# IDE_CF.net
KiCad netlist of a schematic drawn in Altium Designer
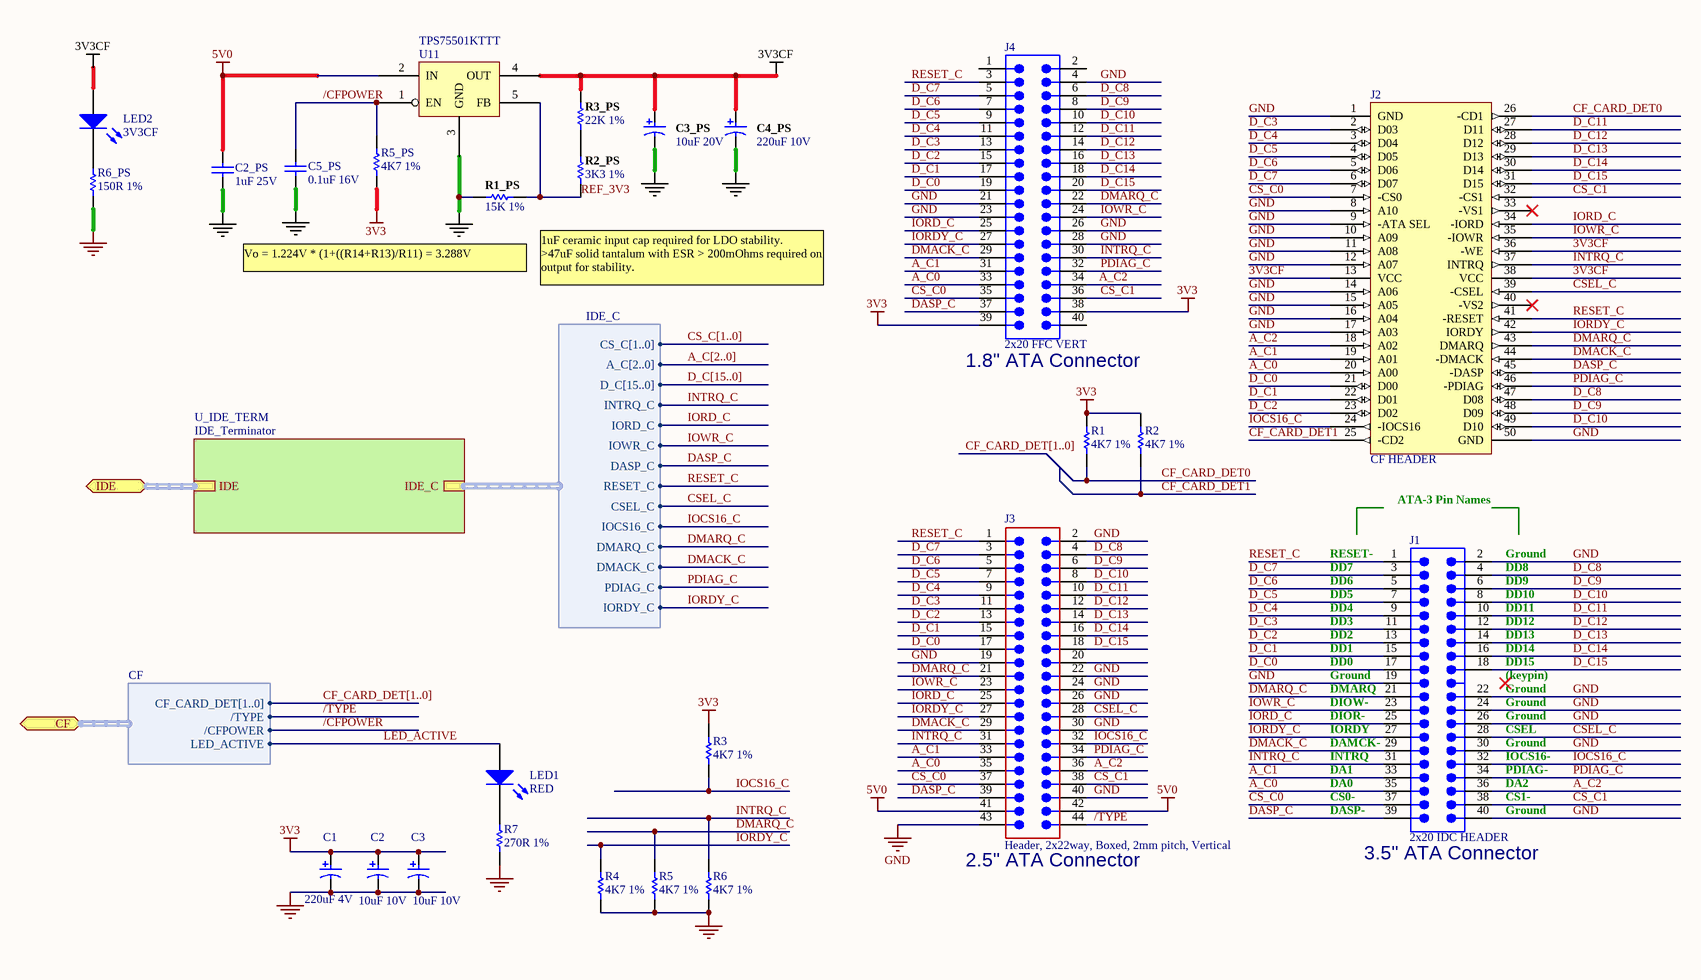
[diagram p0: IDE_CF.SchDoc]

(export (version "E")
  (design (tool "Eeschema 10.0.6"))
  (components
    (comp (ref "C1")
      (value "220uF 4V")
      (footprint "CAPC7343-STAR")
      (description "Capacitor, Tantalum, 220uF-4V-MCCT-D (7343)")
      (fields (field (name "TOLERANCE") "%"))
      (libsource (lib "AltiumDesignLibrary") (part "CAP-P"))
    )
    (comp (ref "C2")
      (value "10uF 10V")
      (footprint "CAPC3528-STAR")
      (description "Capacitor, Tantalum, 10uF 10V MCCT-B (3528)")
      (fields (field (name "TOLERANCE") "%"))
      (libsource (lib "AltiumDesignLibrary") (part "CAP-P"))
    )
    (comp (ref "C2_PS")
      (value "1uF 25V")
      (footprint "CAPC3216-STAR")
      (description "Capacitor, Ceramic, 1uF 10% 25V 1206 (3216) X7R")
      (fields (field (name "TOLERANCE") "10 %"))
      (libsource (lib "AltiumDesignLibrary") (part "CAP-NP"))
    )
    (comp (ref "C3")
      (value "10uF 10V")
      (footprint "CAPC3528-STAR")
      (description "Capacitor, Tantalum, 10uF 10V MCCT-B (3528)")
      (fields (field (name "TOLERANCE") "%"))
      (libsource (lib "AltiumDesignLibrary") (part "CAP-P"))
    )
    (comp (ref "C3_PS")
      (value "10uF 20V")
      (footprint "CAPC3528-STAR")
      (description "Capacitor, Tantalum, 10uF 10% 20V MCCT-B (3528)")
      (fields (field (name "TOLERANCE") "10 %"))
      (libsource (lib "AltiumDesignLibrary") (part "CAP-P"))
    )
    (comp (ref "C4_PS")
      (value "220uF 10V")
      (footprint "CAPC7343-STAR")
      (description "Capacitor, Tantalum, 220uF 10% 10V MCCT-D (7343-31)")
      (fields (field (name "TOLERANCE") "10 %"))
      (libsource (lib "AltiumDesignLibrary") (part "CAP-P"))
    )
    (comp (ref "C5_PS")
      (value "0.1uF 16V")
      (footprint "CAPC1005-STAR")
      (description "Capacitor, Ceramic, 0.1uF 10% 16V 0402 (1005) X7R")
      (fields (field (name "TOLERANCE") "10 %"))
      (libsource (lib "AltiumDesignLibrary") (part "CAP-NP"))
    )
    (comp (ref "J1")
      (value "2x20 IDC HEADER")
      (footprint "918540x324")
      (description "Header, Box 2 x 20 Pin Vertical 2.54mm Pitch")
      (libsource (lib "AltiumDesignLibrary") (part "CON-IDC-2x20-M-STR"))
    )
    (comp (ref "J2")
      (value "CF HEADER")
      (footprint "CF_SM0_635-6H50B")
      (description "Connector, Compact Flash Card Adaptor Top-side")
      (libsource (lib "AltiumDesignLibrary") (part "CON-CF"))
    )
    (comp (ref "J3")
      (value "Header, 2x22way, Boxed, 2mm pitch, Vertical")
      (footprint "HDR2X22-2mm")
      (libsource (lib "AltiumDesignLibrary") (part "CON-IDC-2x22-M-STR-2mm"))
    )
    (comp (ref "J4")
      (value "2x20 FFC VERT")
      (footprint "FFC40-05-VERT")
      (description "Header FFC, 2x20 pin Vertical, 0.5mm")
      (libsource (lib "AltiumDesignLibrary") (part "CON-FFC-2x20-VERT"))
    )
    (comp (ref "LED1")
      (value "RED")
      (footprint "LED2012-STAR")
      (description "LED, Red 0805 (2013) HSMH-C170")
      (libsource (lib "AltiumDesignLibrary") (part "DIO-LED-1S"))
    )
    (comp (ref "LED2")
      (value "3V3CF")
      (footprint "LED2012-STAR")
      (description "LED, Green 0805 (2012) KP-2012SGD")
      (libsource (lib "AltiumDesignLibrary") (part "DIO-LED-1S"))
    )
    (comp (ref "R1")
      (value "4K7 1%")
      (footprint "RESC1005-STAR")
      (description "Resistor, 4K7 1% 0402 (1005)")
      (fields (field (name "TOLERANCE") "1 %"))
      (libsource (lib "AltiumDesignLibrary") (part "RES"))
    )
    (comp (ref "R1_PS")
      (value "15K 1%")
      (footprint "RESC1005-STAR")
      (description "Resistor, 15K 1% 0402 (1005)")
      (fields (field (name "TOLERANCE") "1 %"))
      (libsource (lib "AltiumDesignLibrary") (part "RES"))
    )
    (comp (ref "R2")
      (value "4K7 1%")
      (footprint "RESC1005-STAR")
      (description "Resistor, 4K7 1% 0402 (1005)")
      (fields (field (name "TOLERANCE") "1 %"))
      (libsource (lib "AltiumDesignLibrary") (part "RES"))
    )
    (comp (ref "R2_PS")
      (value "3K3 1%")
      (footprint "RESC1005-STAR")
      (description "Resistor, 3K3 1% 0402 (1005)")
      (fields (field (name "TOLERANCE") "1 %"))
      (libsource (lib "AltiumDesignLibrary") (part "RES"))
    )
    (comp (ref "R3")
      (value "4K7 1%")
      (footprint "RESC1005-STAR")
      (description "Resistor, 4K7 1% 0402 (1005)")
      (fields (field (name "TOLERANCE") "1 %"))
      (libsource (lib "AltiumDesignLibrary") (part "RES"))
    )
    (comp (ref "R3_PS")
      (value "22K 1%")
      (footprint "RESC1005-STAR")
      (description "Resistor, 22K 1% 0402 (1005)")
      (fields (field (name "TOLERANCE") "1 %"))
      (libsource (lib "AltiumDesignLibrary") (part "RES"))
    )
    (comp (ref "R4")
      (value "4K7 1%")
      (footprint "RESC1005-STAR")
      (description "Resistor, 4K7 1% 0402 (1005)")
      (fields (field (name "TOLERANCE") "1 %"))
      (libsource (lib "AltiumDesignLibrary") (part "RES"))
    )
    (comp (ref "R5")
      (value "4K7 1%")
      (footprint "RESC1005-STAR")
      (description "Resistor, 4K7 1% 0402 (1005)")
      (fields (field (name "TOLERANCE") "1 %"))
      (libsource (lib "AltiumDesignLibrary") (part "RES"))
    )
    (comp (ref "R5_PS")
      (value "4K7 1%")
      (footprint "RESC1005-STAR")
      (description "Resistor, 4K7 1% 0402 (1005)")
      (fields (field (name "TOLERANCE") "1 %"))
      (libsource (lib "AltiumDesignLibrary") (part "RES"))
    )
    (comp (ref "R6")
      (value "4K7 1%")
      (footprint "RESC1005-STAR")
      (description "Resistor, 4K7 1% 0402 (1005)")
      (fields (field (name "TOLERANCE") "1 %"))
      (libsource (lib "AltiumDesignLibrary") (part "RES"))
    )
    (comp (ref "R6_PS")
      (value "150R 1%")
      (footprint "RESC1005-STAR")
      (description "Resistor, 150R 1% 0402 (1005)")
      (fields (field (name "TOLERANCE") "1 %"))
      (libsource (lib "AltiumDesignLibrary") (part "RES"))
    )
    (comp (ref "R7")
      (value "270R 1%")
      (footprint "RESC1005-STAR")
      (description "Resistor, 270R 1% 0402 (1005)")
      (fields (field (name "TOLERANCE") "1 %"))
      (libsource (lib "AltiumDesignLibrary") (part "RES"))
    )
    (comp (ref "U11")
      (value "TPS75501KTTT")
      (footprint "TO-263")
      (description "TPS75501KTTT, 5A, Low Dropout, Adjustable, Linear Voltage Regulator, TO-263")
      (libsource (lib "AltiumDesignLibrary") (part "TPS75501"))
    )
  )
  (nets
    (net (code "4") (name "/A_C0") (class "Default")
      (node (ref "J1") (pin "35") (pinfunction "35_35") (pintype "passive"))
      (node (ref "J2") (pin "20") (pinfunction "A00_20") (pintype "input"))
      (node (ref "J3") (pin "35") (pinfunction "35_35") (pintype "passive"))
      (node (ref "J4") (pin "33") (pinfunction "33_33") (pintype "passive"))
    )
    (net (code "5") (name "/A_C1") (class "Default")
      (node (ref "J1") (pin "33") (pinfunction "33_33") (pintype "passive"))
      (node (ref "J2") (pin "19") (pinfunction "A01_19") (pintype "input"))
      (node (ref "J3") (pin "33") (pinfunction "33_33") (pintype "passive"))
      (node (ref "J4") (pin "31") (pinfunction "31_31") (pintype "passive"))
    )
    (net (code "6") (name "/A_C2") (class "Default")
      (node (ref "J1") (pin "36") (pinfunction "36_36") (pintype "passive"))
      (node (ref "J2") (pin "18") (pinfunction "A02_18") (pintype "input"))
      (node (ref "J3") (pin "36") (pinfunction "36_36") (pintype "passive"))
      (node (ref "J4") (pin "34") (pinfunction "34_34") (pintype "passive"))
    )
    (net (code "8") (name "/CF_CARD_DET0") (class "Default")
      (node (ref "J2") (pin "26") (pinfunction "-CD1_26") (pintype "output"))
      (node (ref "R1") (pin "2") (pinfunction "2_2") (pintype "passive"))
    )
    (net (code "9") (name "/CF_CARD_DET1") (class "Default")
      (node (ref "J2") (pin "25") (pinfunction "-CD2_25") (pintype "output"))
      (node (ref "R2") (pin "2") (pinfunction "2_2") (pintype "passive"))
    )
    (net (code "11") (name "/CSEL_C") (class "Default")
      (node (ref "J1") (pin "28") (pinfunction "28_28") (pintype "passive"))
      (node (ref "J2") (pin "39") (pinfunction "-CSEL_39") (pintype "input"))
      (node (ref "J3") (pin "28") (pinfunction "28_28") (pintype "passive"))
    )
    (net (code "12") (name "/CS_C0") (class "Default")
      (node (ref "J1") (pin "37") (pinfunction "37_37") (pintype "passive"))
      (node (ref "J2") (pin "7") (pinfunction "-CS0_7") (pintype "input"))
      (node (ref "J3") (pin "37") (pinfunction "37_37") (pintype "passive"))
      (node (ref "J4") (pin "35") (pinfunction "35_35") (pintype "passive"))
    )
    (net (code "13") (name "/CS_C1") (class "Default")
      (node (ref "J1") (pin "38") (pinfunction "38_38") (pintype "passive"))
      (node (ref "J2") (pin "32") (pinfunction "-CS1_32") (pintype "input"))
      (node (ref "J3") (pin "38") (pinfunction "38_38") (pintype "passive"))
      (node (ref "J4") (pin "36") (pinfunction "36_36") (pintype "passive"))
    )
    (net (code "15") (name "/DASP_C") (class "Default")
      (node (ref "J1") (pin "39") (pinfunction "39_39") (pintype "passive"))
      (node (ref "J2") (pin "45") (pinfunction "-DASP_45") (pintype "bidirectional"))
      (node (ref "J3") (pin "39") (pinfunction "39_39") (pintype "passive"))
      (node (ref "J4") (pin "37") (pinfunction "37_37") (pintype "passive"))
    )
    (net (code "16") (name "/DMACK_C") (class "Default")
      (node (ref "J1") (pin "29") (pinfunction "29_29") (pintype "passive"))
      (node (ref "J2") (pin "44") (pinfunction "-DMACK_44") (pintype "input"))
      (node (ref "J3") (pin "29") (pinfunction "29_29") (pintype "passive"))
      (node (ref "J4") (pin "29") (pinfunction "29_29") (pintype "passive"))
    )
    (net (code "17") (name "/DMARQ_C") (class "Default")
      (node (ref "J1") (pin "21") (pinfunction "21_21") (pintype "passive"))
      (node (ref "J2") (pin "43") (pinfunction "DMARQ_43") (pintype "output"))
      (node (ref "J3") (pin "21") (pinfunction "21_21") (pintype "passive"))
      (node (ref "J4") (pin "22") (pinfunction "22_22") (pintype "passive"))
      (node (ref "R5") (pin "1") (pinfunction "1_1") (pintype "passive"))
    )
    (net (code "18") (name "/D_C0") (class "Default")
      (node (ref "J1") (pin "17") (pinfunction "17_17") (pintype "passive"))
      (node (ref "J2") (pin "21") (pinfunction "D00_21") (pintype "bidirectional"))
      (node (ref "J3") (pin "17") (pinfunction "17_17") (pintype "passive"))
      (node (ref "J4") (pin "19") (pinfunction "19_19") (pintype "passive"))
    )
    (net (code "19") (name "/D_C1") (class "Default")
      (node (ref "J1") (pin "15") (pinfunction "15_15") (pintype "passive"))
      (node (ref "J2") (pin "22") (pinfunction "D01_22") (pintype "bidirectional"))
      (node (ref "J3") (pin "15") (pinfunction "15_15") (pintype "passive"))
      (node (ref "J4") (pin "17") (pinfunction "17_17") (pintype "passive"))
    )
    (net (code "20") (name "/D_C2") (class "Default")
      (node (ref "J1") (pin "13") (pinfunction "13_13") (pintype "passive"))
      (node (ref "J2") (pin "23") (pinfunction "D02_23") (pintype "bidirectional"))
      (node (ref "J3") (pin "13") (pinfunction "13_13") (pintype "passive"))
      (node (ref "J4") (pin "15") (pinfunction "15_15") (pintype "passive"))
    )
    (net (code "21") (name "/D_C3") (class "Default")
      (node (ref "J1") (pin "11") (pinfunction "11_11") (pintype "passive"))
      (node (ref "J2") (pin "2") (pinfunction "D03_2") (pintype "bidirectional"))
      (node (ref "J3") (pin "11") (pinfunction "11_11") (pintype "passive"))
      (node (ref "J4") (pin "13") (pinfunction "13_13") (pintype "passive"))
    )
    (net (code "22") (name "/D_C4") (class "Default")
      (node (ref "J1") (pin "9") (pinfunction "9_9") (pintype "passive"))
      (node (ref "J2") (pin "3") (pinfunction "D04_3") (pintype "bidirectional"))
      (node (ref "J3") (pin "9") (pinfunction "9_9") (pintype "passive"))
      (node (ref "J4") (pin "11") (pinfunction "11_11") (pintype "passive"))
    )
    (net (code "23") (name "/D_C5") (class "Default")
      (node (ref "J1") (pin "7") (pinfunction "7_7") (pintype "passive"))
      (node (ref "J2") (pin "4") (pinfunction "D05_4") (pintype "bidirectional"))
      (node (ref "J3") (pin "7") (pinfunction "7_7") (pintype "passive"))
      (node (ref "J4") (pin "9") (pinfunction "9_9") (pintype "passive"))
    )
    (net (code "24") (name "/D_C6") (class "Default")
      (node (ref "J1") (pin "5") (pinfunction "5_5") (pintype "passive"))
      (node (ref "J2") (pin "5") (pinfunction "D06_5") (pintype "bidirectional"))
      (node (ref "J3") (pin "5") (pinfunction "5_5") (pintype "passive"))
      (node (ref "J4") (pin "7") (pinfunction "7_7") (pintype "passive"))
    )
    (net (code "25") (name "/D_C7") (class "Default")
      (node (ref "J1") (pin "3") (pinfunction "3_3") (pintype "passive"))
      (node (ref "J2") (pin "6") (pinfunction "D07_6") (pintype "bidirectional"))
      (node (ref "J3") (pin "3") (pinfunction "3_3") (pintype "passive"))
      (node (ref "J4") (pin "5") (pinfunction "5_5") (pintype "passive"))
    )
    (net (code "26") (name "/D_C8") (class "Default")
      (node (ref "J1") (pin "4") (pinfunction "4_4") (pintype "passive"))
      (node (ref "J2") (pin "47") (pinfunction "D08_47") (pintype "bidirectional"))
      (node (ref "J3") (pin "4") (pinfunction "4_4") (pintype "passive"))
      (node (ref "J4") (pin "6") (pinfunction "6_6") (pintype "passive"))
    )
    (net (code "27") (name "/D_C9") (class "Default")
      (node (ref "J1") (pin "6") (pinfunction "6_6") (pintype "passive"))
      (node (ref "J2") (pin "48") (pinfunction "D09_48") (pintype "bidirectional"))
      (node (ref "J3") (pin "6") (pinfunction "6_6") (pintype "passive"))
      (node (ref "J4") (pin "8") (pinfunction "8_8") (pintype "passive"))
    )
    (net (code "28") (name "/D_C10") (class "Default")
      (node (ref "J1") (pin "8") (pinfunction "8_8") (pintype "passive"))
      (node (ref "J2") (pin "49") (pinfunction "D10_49") (pintype "bidirectional"))
      (node (ref "J3") (pin "8") (pinfunction "8_8") (pintype "passive"))
      (node (ref "J4") (pin "10") (pinfunction "10_10") (pintype "passive"))
    )
    (net (code "29") (name "/D_C11") (class "Default")
      (node (ref "J1") (pin "10") (pinfunction "10_10") (pintype "passive"))
      (node (ref "J2") (pin "27") (pinfunction "D11_27") (pintype "bidirectional"))
      (node (ref "J3") (pin "10") (pinfunction "10_10") (pintype "passive"))
      (node (ref "J4") (pin "12") (pinfunction "12_12") (pintype "passive"))
    )
    (net (code "30") (name "/D_C12") (class "Default")
      (node (ref "J1") (pin "12") (pinfunction "12_12") (pintype "passive"))
      (node (ref "J2") (pin "28") (pinfunction "D12_28") (pintype "bidirectional"))
      (node (ref "J3") (pin "12") (pinfunction "12_12") (pintype "passive"))
      (node (ref "J4") (pin "14") (pinfunction "14_14") (pintype "passive"))
    )
    (net (code "31") (name "/D_C13") (class "Default")
      (node (ref "J1") (pin "14") (pinfunction "14_14") (pintype "passive"))
      (node (ref "J2") (pin "29") (pinfunction "D13_29") (pintype "bidirectional"))
      (node (ref "J3") (pin "14") (pinfunction "14_14") (pintype "passive"))
      (node (ref "J4") (pin "16") (pinfunction "16_16") (pintype "passive"))
    )
    (net (code "32") (name "/D_C14") (class "Default")
      (node (ref "J1") (pin "16") (pinfunction "16_16") (pintype "passive"))
      (node (ref "J2") (pin "30") (pinfunction "D14_30") (pintype "bidirectional"))
      (node (ref "J3") (pin "16") (pinfunction "16_16") (pintype "passive"))
      (node (ref "J4") (pin "18") (pinfunction "18_18") (pintype "passive"))
    )
    (net (code "33") (name "/D_C15") (class "Default")
      (node (ref "J1") (pin "18") (pinfunction "18_18") (pintype "passive"))
      (node (ref "J2") (pin "31") (pinfunction "D15_31") (pintype "bidirectional"))
      (node (ref "J3") (pin "18") (pinfunction "18_18") (pintype "passive"))
      (node (ref "J4") (pin "20") (pinfunction "20_20") (pintype "passive"))
    )
    (net (code "36") (name "/INTRQ_C") (class "Default")
      (node (ref "J1") (pin "31") (pinfunction "31_31") (pintype "passive"))
      (node (ref "J2") (pin "37") (pinfunction "INTRQ_37") (pintype "output"))
      (node (ref "J3") (pin "31") (pinfunction "31_31") (pintype "passive"))
      (node (ref "J4") (pin "30") (pinfunction "30_30") (pintype "passive"))
      (node (ref "R6") (pin "1") (pinfunction "1_1") (pintype "passive"))
    )
    (net (code "37") (name "/IOCS16_C") (class "Default")
      (node (ref "J1") (pin "32") (pinfunction "32_32") (pintype "passive"))
      (node (ref "J2") (pin "24") (pinfunction "-IOCS16_24") (pintype "output"))
      (node (ref "J3") (pin "32") (pinfunction "32_32") (pintype "passive"))
      (node (ref "R3") (pin "2") (pinfunction "2_2") (pintype "passive"))
    )
    (net (code "38") (name "/IORDY_C") (class "Default")
      (node (ref "J1") (pin "27") (pinfunction "27_27") (pintype "passive"))
      (node (ref "J2") (pin "42") (pinfunction "IORDY_42") (pintype "output"))
      (node (ref "J3") (pin "27") (pinfunction "27_27") (pintype "passive"))
      (node (ref "J4") (pin "27") (pinfunction "27_27") (pintype "passive"))
      (node (ref "R4") (pin "1") (pinfunction "1_1") (pintype "passive"))
    )
    (net (code "39") (name "/IORD_C") (class "Default")
      (node (ref "J1") (pin "25") (pinfunction "25_25") (pintype "passive"))
      (node (ref "J2") (pin "34") (pinfunction "-IORD_34") (pintype "input"))
      (node (ref "J3") (pin "25") (pinfunction "25_25") (pintype "passive"))
      (node (ref "J4") (pin "25") (pinfunction "25_25") (pintype "passive"))
    )
    (net (code "40") (name "/IOWR_C") (class "Default")
      (node (ref "J1") (pin "23") (pinfunction "23_23") (pintype "passive"))
      (node (ref "J2") (pin "35") (pinfunction "-IOWR_35") (pintype "input"))
      (node (ref "J3") (pin "23") (pinfunction "23_23") (pintype "passive"))
      (node (ref "J4") (pin "24") (pinfunction "24_24") (pintype "passive"))
    )
    (net (code "41") (name "/LED_ACTIVE") (class "Default")
      (node (ref "LED1") (pin "1") (pinfunction "A_1") (pintype "passive"))
    )
    (net (code "42") (name "/PDIAG_C") (class "Default")
      (node (ref "J1") (pin "34") (pinfunction "34_34") (pintype "passive"))
      (node (ref "J2") (pin "46") (pinfunction "-PDIAG_46") (pintype "bidirectional"))
      (node (ref "J3") (pin "34") (pinfunction "34_34") (pintype "passive"))
      (node (ref "J4") (pin "32") (pinfunction "32_32") (pintype "passive"))
    )
    (net (code "43") (name "/REF_3V3") (class "Default")
      (node (ref "R1_PS") (pin "2") (pinfunction "2_2") (pintype "passive"))
      (node (ref "R2_PS") (pin "1") (pinfunction "1_1") (pintype "passive"))
      (node (ref "U11") (pin "5") (pinfunction "FB_5") (pintype "passive"))
    )
    (net (code "44") (name "/RESET_C") (class "Default")
      (node (ref "J1") (pin "1") (pinfunction "1_1") (pintype "passive"))
      (node (ref "J2") (pin "41") (pinfunction "-RESET_41") (pintype "input"))
      (node (ref "J3") (pin "1") (pinfunction "1_1") (pintype "passive"))
      (node (ref "J4") (pin "3") (pinfunction "3_3") (pintype "passive"))
    )
    (net (code "47") (name "/{slash}CFPOWER") (class "Default")
      (node (ref "C5_PS") (pin "1") (pinfunction "1_1") (pintype "passive"))
      (node (ref "R5_PS") (pin "1") (pinfunction "1_1") (pintype "passive"))
      (node (ref "U11") (pin "1") (pinfunction "EN_1") (pintype "passive"))
    )
    (net (code "48") (name "/{slash}TYPE") (class "Default")
      (node (ref "J3") (pin "44") (pinfunction "44_44") (pintype "passive"))
    )
    (net (code "49") (name "3V3") (class "Default")
      (node (ref "C1") (pin "1") (pinfunction "1_1") (pintype "passive"))
      (node (ref "C2") (pin "1") (pinfunction "1_1") (pintype "passive"))
      (node (ref "C3") (pin "1") (pinfunction "1_1") (pintype "passive"))
      (node (ref "J4") (pin "38") (pinfunction "38_38") (pintype "passive"))
      (node (ref "J4") (pin "39") (pinfunction "39_39") (pintype "passive"))
      (node (ref "R1") (pin "1") (pinfunction "1_1") (pintype "passive"))
      (node (ref "R2") (pin "1") (pinfunction "1_1") (pintype "passive"))
      (node (ref "R3") (pin "1") (pinfunction "1_1") (pintype "passive"))
      (node (ref "R5_PS") (pin "2") (pinfunction "2_2") (pintype "passive"))
    )
    (net (code "50") (name "3V3CF") (class "Default")
      (node (ref "C3_PS") (pin "1") (pinfunction "1_1") (pintype "passive"))
      (node (ref "C4_PS") (pin "1") (pinfunction "1_1") (pintype "passive"))
      (node (ref "J2") (pin "13") (pinfunction "VCC_13") (pintype "power_in"))
      (node (ref "J2") (pin "36") (pinfunction "-WE_36") (pintype "input"))
      (node (ref "J2") (pin "38") (pinfunction "VCC_38") (pintype "power_in"))
      (node (ref "LED2") (pin "1") (pinfunction "A_1") (pintype "passive"))
      (node (ref "R3_PS") (pin "2") (pinfunction "2_2") (pintype "passive"))
      (node (ref "U11") (pin "4") (pinfunction "OUT_4") (pintype "passive"))
    )
    (net (code "51") (name "5V0") (class "Default")
      (node (ref "C2_PS") (pin "1") (pinfunction "1_1") (pintype "passive"))
      (node (ref "J3") (pin "41") (pinfunction "41_41") (pintype "passive"))
      (node (ref "J3") (pin "42") (pinfunction "42_42") (pintype "passive"))
      (node (ref "U11") (pin "2") (pinfunction "IN_2") (pintype "passive"))
    )
    (net (code "52") (name "GND") (class "Default")
      (node (ref "C1") (pin "2") (pinfunction "2_2") (pintype "passive"))
      (node (ref "C2") (pin "2") (pinfunction "2_2") (pintype "passive"))
      (node (ref "C2_PS") (pin "2") (pinfunction "2_2") (pintype "passive"))
      (node (ref "C3") (pin "2") (pinfunction "2_2") (pintype "passive"))
      (node (ref "C3_PS") (pin "2") (pinfunction "2_2") (pintype "passive"))
      (node (ref "C4_PS") (pin "2") (pinfunction "2_2") (pintype "passive"))
      (node (ref "C5_PS") (pin "2") (pinfunction "2_2") (pintype "passive"))
      (node (ref "J1") (pin "19") (pinfunction "19_19") (pintype "passive"))
      (node (ref "J1") (pin "2") (pinfunction "2_2") (pintype "passive"))
      (node (ref "J1") (pin "22") (pinfunction "22_22") (pintype "passive"))
      (node (ref "J1") (pin "24") (pinfunction "24_24") (pintype "passive"))
      (node (ref "J1") (pin "26") (pinfunction "26_26") (pintype "passive"))
      (node (ref "J1") (pin "30") (pinfunction "30_30") (pintype "passive"))
      (node (ref "J1") (pin "40") (pinfunction "40_40") (pintype "passive"))
      (node (ref "J2") (pin "1") (pinfunction "GND_1") (pintype "power_in"))
      (node (ref "J2") (pin "10") (pinfunction "A09_10") (pintype "input"))
      (node (ref "J2") (pin "11") (pinfunction "A08_11") (pintype "input"))
      (node (ref "J2") (pin "12") (pinfunction "A07_12") (pintype "input"))
      (node (ref "J2") (pin "14") (pinfunction "A06_14") (pintype "input"))
      (node (ref "J2") (pin "15") (pinfunction "A05_15") (pintype "input"))
      (node (ref "J2") (pin "16") (pinfunction "A04_16") (pintype "input"))
      (node (ref "J2") (pin "17") (pinfunction "A03_17") (pintype "input"))
      (node (ref "J2") (pin "50") (pinfunction "GND_50") (pintype "power_in"))
      (node (ref "J2") (pin "8") (pinfunction "A10_8") (pintype "input"))
      (node (ref "J2") (pin "9") (pinfunction "-ATA_SEL_9") (pintype "input"))
      (node (ref "J3") (pin "19") (pinfunction "19_19") (pintype "passive"))
      (node (ref "J3") (pin "2") (pinfunction "2_2") (pintype "passive"))
      (node (ref "J3") (pin "22") (pinfunction "22_22") (pintype "passive"))
      (node (ref "J3") (pin "24") (pinfunction "24_24") (pintype "passive"))
      (node (ref "J3") (pin "26") (pinfunction "26_26") (pintype "passive"))
      (node (ref "J3") (pin "30") (pinfunction "30_30") (pintype "passive"))
      (node (ref "J3") (pin "40") (pinfunction "40_40") (pintype "passive"))
      (node (ref "J3") (pin "43") (pinfunction "43_43") (pintype "passive"))
      (node (ref "J4") (pin "21") (pinfunction "21_21") (pintype "passive"))
      (node (ref "J4") (pin "23") (pinfunction "23_23") (pintype "passive"))
      (node (ref "J4") (pin "26") (pinfunction "26_26") (pintype "passive"))
      (node (ref "J4") (pin "28") (pinfunction "28_28") (pintype "passive"))
      (node (ref "J4") (pin "4") (pinfunction "4_4") (pintype "passive"))
      (node (ref "R1_PS") (pin "1") (pinfunction "1_1") (pintype "passive"))
      (node (ref "R4") (pin "2") (pinfunction "2_2") (pintype "passive"))
      (node (ref "R5") (pin "2") (pinfunction "2_2") (pintype "passive"))
      (node (ref "R6") (pin "2") (pinfunction "2_2") (pintype "passive"))
      (node (ref "R6_PS") (pin "2") (pinfunction "2_2") (pintype "passive"))
      (node (ref "R7") (pin "1") (pinfunction "1_1") (pintype "passive"))
      (node (ref "U11") (pin "3") (pinfunction "GND_3") (pintype "passive"))
    )
    (net (code "53") (name "Net-(LED1-K)") (class "Default")
      (node (ref "LED1") (pin "2") (pinfunction "K_2") (pintype "passive"))
      (node (ref "R7") (pin "2") (pinfunction "2_2") (pintype "passive"))
    )
    (net (code "54") (name "Net-(LED2-K)") (class "Default")
      (node (ref "LED2") (pin "2") (pinfunction "K_2") (pintype "passive"))
      (node (ref "R6_PS") (pin "1") (pinfunction "1_1") (pintype "passive"))
    )
    (net (code "55") (name "Net-(R2_PS-Pad2)") (class "Default")
      (node (ref "R2_PS") (pin "2") (pinfunction "2_2") (pintype "passive"))
      (node (ref "R3_PS") (pin "1") (pinfunction "1_1") (pintype "passive"))
    )
    (net (code "56") (name "unconnected-(J2--VS1-Pad33)") (class "Default")
      (node (ref "J2") (pin "33") (pinfunction "-VS1_33") (pintype "output+no_connect"))
    )
    (net (code "57") (name "unconnected-(J2--VS2-Pad40)") (class "Default")
      (node (ref "J2") (pin "40") (pinfunction "-VS2_40") (pintype "output+no_connect"))
    )
    (net (code "58") (name "unconnected-(J3-Pad20)") (class "Default")
      (node (ref "J3") (pin "20") (pinfunction "20_20") (pintype "passive"))
    )
    (net (code "59") (name "unconnected-(J4-Pad1)") (class "Default")
      (node (ref "J4") (pin "1") (pinfunction "1_1") (pintype "passive"))
    )
    (net (code "60") (name "unconnected-(J4-Pad2)") (class "Default")
      (node (ref "J4") (pin "2") (pinfunction "2_2") (pintype "passive"))
    )
    (net (code "61") (name "unconnected-(J4-Pad40)") (class "Default")
      (node (ref "J4") (pin "40") (pinfunction "40_40") (pintype "passive"))
    )
  )
)
